# PowerModuleCell.net
KiCad netlist of a schematic drawn in Altium Designer
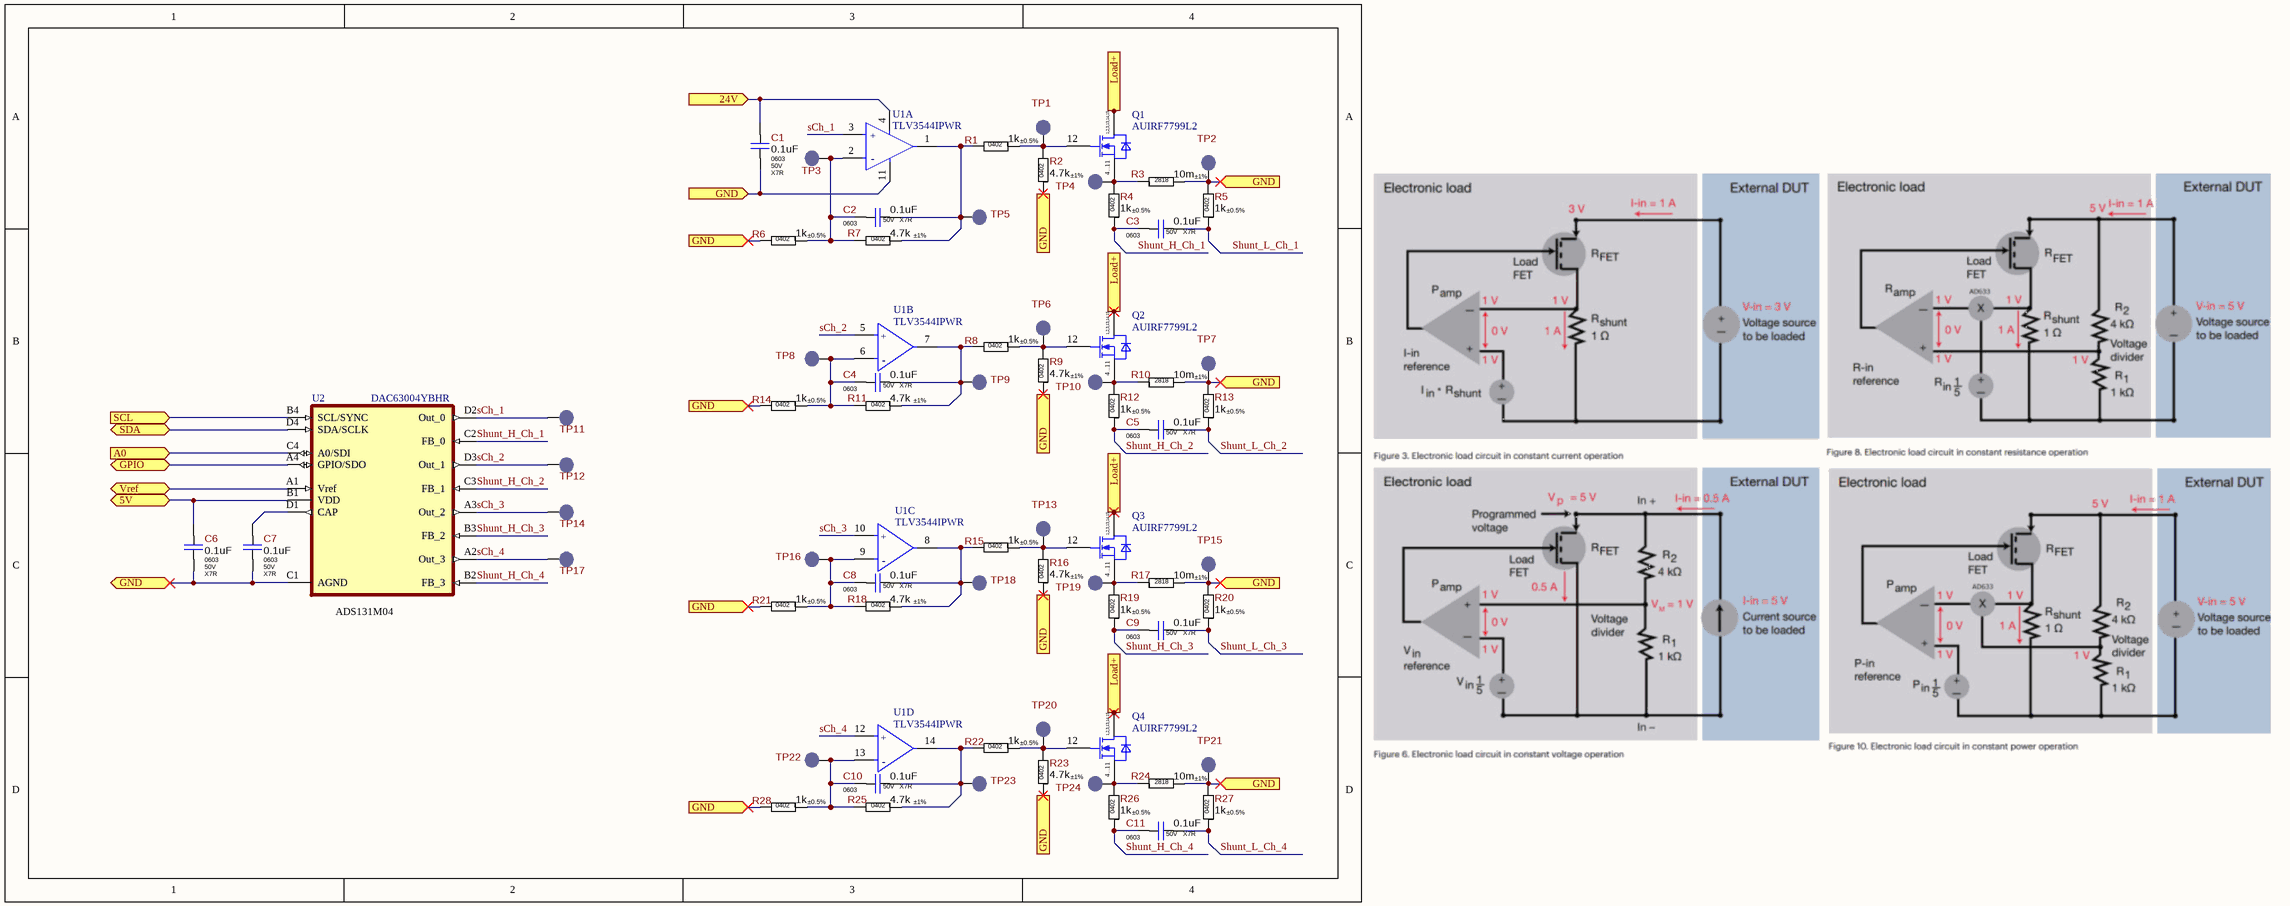
[diagram p0: PowerModuleCell.SchDoc]

(export (version "E")
  (design (tool "Eeschema 10.0.6"))
  (components
    (comp (ref "C1")
      (value "0.1uF")
      (footprint "C_CERAMIC_0603_MED")
      (description "100nF 50V X7R ±10% 0603 Ceramic Capacitor RoHS")
      (fields
        (field (name "PART NUMBER") "CL10B104KB8NNNC")
        (field (name "MANUFACTURER") "Samsung Electro-Mechanics")
        (field (name "PACKAGE") "0603")
        (field (name "VOLTAGE") "50V")
        (field (name "DIELECTRIC TYPE") "X7R")
      )
      (libsource (lib "EL.XXX.T01") (part "CL10B104KB8NNNC"))
    )
    (comp (ref "C2")
      (value "0.1uF")
      (footprint "C_CERAMIC_0603_MED")
      (description "100nF 50V X7R ±10% 0603 Ceramic Capacitor RoHS")
      (fields
        (field (name "PART NUMBER") "CL10B104KB8NNNC")
        (field (name "MANUFACTURER") "Samsung Electro-Mechanics")
        (field (name "PACKAGE") "0603")
        (field (name "VOLTAGE") "50V")
        (field (name "DIELECTRIC TYPE") "X7R")
      )
      (libsource (lib "EL.XXX.T01") (part "CL10B104KB8NNNC"))
    )
    (comp (ref "C3")
      (value "0.1uF")
      (footprint "C_CERAMIC_0603_MED")
      (description "100nF 50V X7R ±10% 0603 Ceramic Capacitor RoHS")
      (fields
        (field (name "PART NUMBER") "CL10B104KB8NNNC")
        (field (name "MANUFACTURER") "Samsung Electro-Mechanics")
        (field (name "PACKAGE") "0603")
        (field (name "VOLTAGE") "50V")
        (field (name "DIELECTRIC TYPE") "X7R")
      )
      (libsource (lib "EL.XXX.T01") (part "CL10B104KB8NNNC"))
    )
    (comp (ref "C4")
      (value "0.1uF")
      (footprint "C_CERAMIC_0603_MED")
      (description "100nF 50V X7R ±10% 0603 Ceramic Capacitor RoHS")
      (fields
        (field (name "PART NUMBER") "CL10B104KB8NNNC")
        (field (name "MANUFACTURER") "Samsung Electro-Mechanics")
        (field (name "PACKAGE") "0603")
        (field (name "VOLTAGE") "50V")
        (field (name "DIELECTRIC TYPE") "X7R")
      )
      (libsource (lib "EL.XXX.T01") (part "CL10B104KB8NNNC"))
    )
    (comp (ref "C5")
      (value "0.1uF")
      (footprint "C_CERAMIC_0603_MED")
      (description "100nF 50V X7R ±10% 0603 Ceramic Capacitor RoHS")
      (fields
        (field (name "PART NUMBER") "CL10B104KB8NNNC")
        (field (name "MANUFACTURER") "Samsung Electro-Mechanics")
        (field (name "PACKAGE") "0603")
        (field (name "VOLTAGE") "50V")
        (field (name "DIELECTRIC TYPE") "X7R")
      )
      (libsource (lib "EL.XXX.T01") (part "CL10B104KB8NNNC"))
    )
    (comp (ref "C6")
      (value "0.1uF")
      (footprint "C_CERAMIC_0603_MED")
      (description "100nF 50V X7R ±10% 0603 Ceramic Capacitor RoHS")
      (fields
        (field (name "PART NUMBER") "CL10B104KB8NNNC")
        (field (name "MANUFACTURER") "Samsung Electro-Mechanics")
        (field (name "PACKAGE") "0603")
        (field (name "VOLTAGE") "50V")
        (field (name "DIELECTRIC TYPE") "X7R")
      )
      (libsource (lib "EL.XXX.T01") (part "CL10B104KB8NNNC"))
    )
    (comp (ref "C7")
      (value "0.1uF")
      (footprint "C_CERAMIC_0603_MED")
      (description "100nF 50V X7R ±10% 0603 Ceramic Capacitor RoHS")
      (fields
        (field (name "PART NUMBER") "CL10B104KB8NNNC")
        (field (name "MANUFACTURER") "Samsung Electro-Mechanics")
        (field (name "PACKAGE") "0603")
        (field (name "VOLTAGE") "50V")
        (field (name "DIELECTRIC TYPE") "X7R")
      )
      (libsource (lib "EL.XXX.T01") (part "CL10B104KB8NNNC"))
    )
    (comp (ref "C8")
      (value "0.1uF")
      (footprint "C_CERAMIC_0603_MED")
      (description "100nF 50V X7R ±10% 0603 Ceramic Capacitor RoHS")
      (fields
        (field (name "PART NUMBER") "CL10B104KB8NNNC")
        (field (name "MANUFACTURER") "Samsung Electro-Mechanics")
        (field (name "PACKAGE") "0603")
        (field (name "VOLTAGE") "50V")
        (field (name "DIELECTRIC TYPE") "X7R")
      )
      (libsource (lib "EL.XXX.T01") (part "CL10B104KB8NNNC"))
    )
    (comp (ref "C9")
      (value "0.1uF")
      (footprint "C_CERAMIC_0603_MED")
      (description "100nF 50V X7R ±10% 0603 Ceramic Capacitor RoHS")
      (fields
        (field (name "PART NUMBER") "CL10B104KB8NNNC")
        (field (name "MANUFACTURER") "Samsung Electro-Mechanics")
        (field (name "PACKAGE") "0603")
        (field (name "VOLTAGE") "50V")
        (field (name "DIELECTRIC TYPE") "X7R")
      )
      (libsource (lib "EL.XXX.T01") (part "CL10B104KB8NNNC"))
    )
    (comp (ref "C10")
      (value "0.1uF")
      (footprint "C_CERAMIC_0603_MED")
      (description "100nF 50V X7R ±10% 0603 Ceramic Capacitor RoHS")
      (fields
        (field (name "PART NUMBER") "CL10B104KB8NNNC")
        (field (name "MANUFACTURER") "Samsung Electro-Mechanics")
        (field (name "PACKAGE") "0603")
        (field (name "VOLTAGE") "50V")
        (field (name "DIELECTRIC TYPE") "X7R")
      )
      (libsource (lib "EL.XXX.T01") (part "CL10B104KB8NNNC"))
    )
    (comp (ref "C11")
      (value "0.1uF")
      (footprint "C_CERAMIC_0603_MED")
      (description "100nF 50V X7R ±10% 0603 Ceramic Capacitor RoHS")
      (fields
        (field (name "PART NUMBER") "CL10B104KB8NNNC")
        (field (name "MANUFACTURER") "Samsung Electro-Mechanics")
        (field (name "PACKAGE") "0603")
        (field (name "VOLTAGE") "50V")
        (field (name "DIELECTRIC TYPE") "X7R")
      )
      (libsource (lib "EL.XXX.T01") (part "CL10B104KB8NNNC"))
    )
    (comp (ref "Q1")
      (value "AUIRF7799L2")
      (footprint "DIRECTFET-L8-V")
      (fields (field (name "PART NUMBER") "AUIRF7799L2TR") (field (name "MANUFACTURER") "Infineon"))
      (libsource (lib "EL.XXX.T01") (part "AUIRF7799L2"))
    )
    (comp (ref "Q2")
      (value "AUIRF7799L2")
      (footprint "DIRECTFET-L8-V")
      (fields (field (name "PART NUMBER") "AUIRF7799L2TR") (field (name "MANUFACTURER") "Infineon"))
      (libsource (lib "EL.XXX.T01") (part "AUIRF7799L2"))
    )
    (comp (ref "Q3")
      (value "AUIRF7799L2")
      (footprint "DIRECTFET-L8-V")
      (fields (field (name "PART NUMBER") "AUIRF7799L2TR") (field (name "MANUFACTURER") "Infineon"))
      (libsource (lib "EL.XXX.T01") (part "AUIRF7799L2"))
    )
    (comp (ref "Q4")
      (value "AUIRF7799L2")
      (footprint "DIRECTFET-L8-V")
      (fields (field (name "PART NUMBER") "AUIRF7799L2TR") (field (name "MANUFACTURER") "Infineon"))
      (libsource (lib "EL.XXX.T01") (part "AUIRF7799L2"))
    )
    (comp (ref "R1")
      (value "1k")
      (footprint "R_ANY_CHIP_0402_HI")
      (description "1 kOhms ±0.5% 1/16W 0402 Thick Film Resistor")
      (fields
        (field (name "PART NUMBER") "RC0402DR-071KL")
        (field (name "MANUFACTURER") "Yageo")
        (field (name "TOLERANCE") "±0.5%")
        (field (name "PACKAGE") "0402")
      )
      (libsource (lib "EL.XXX.T01") (part "RC0402DR-071KL"))
    )
    (comp (ref "R2")
      (value "4.7k")
      (footprint "R_ANY_CHIP_0402_HI")
      (description "4.7 kOhms ±1% 1/16W 0402 Thick Film Resistor")
      (fields
        (field (name "PART NUMBER") "RC0402FR-074K7L")
        (field (name "MANUFACTURER") "Yageo")
        (field (name "TOLERANCE") "±1%")
        (field (name "PACKAGE") "0402")
      )
      (libsource (lib "EL.XXX.T01") (part "RC0402FR-074K7L"))
    )
    (comp (ref "R3")
      (value "10m")
      (footprint "WSHP2818")
      (description "Current Sense Resistors - SMD 10W .010ohms 1%")
      (fields
        (field (name "PART NUMBER") "WSHP2818R0100FEA")
        (field (name "MANUFACTURER") "Vishay")
        (field (name "TOLERANCE") "±1%")
        (field (name "PACKAGE") "2818")
      )
      (libsource (lib "EL.XXX.T01") (part "WSHP2818R0100FEA"))
    )
    (comp (ref "R4")
      (value "1k")
      (footprint "R_ANY_CHIP_0402_HI")
      (description "1 kOhms ±0.5% 1/16W 0402 Thick Film Resistor")
      (fields
        (field (name "PART NUMBER") "RC0402DR-071KL")
        (field (name "MANUFACTURER") "Yageo")
        (field (name "TOLERANCE") "±0.5%")
        (field (name "PACKAGE") "0402")
      )
      (libsource (lib "EL.XXX.T01") (part "RC0402DR-071KL"))
    )
    (comp (ref "R5")
      (value "1k")
      (footprint "R_ANY_CHIP_0402_HI")
      (description "1 kOhms ±0.5% 1/16W 0402 Thick Film Resistor")
      (fields
        (field (name "PART NUMBER") "RC0402DR-071KL")
        (field (name "MANUFACTURER") "Yageo")
        (field (name "TOLERANCE") "±0.5%")
        (field (name "PACKAGE") "0402")
      )
      (libsource (lib "EL.XXX.T01") (part "RC0402DR-071KL"))
    )
    (comp (ref "R6")
      (value "1k")
      (footprint "R_ANY_CHIP_0402_HI")
      (description "1 kOhms ±0.5% 1/16W 0402 Thick Film Resistor")
      (fields
        (field (name "PART NUMBER") "RC0402DR-071KL")
        (field (name "MANUFACTURER") "Yageo")
        (field (name "TOLERANCE") "±0.5%")
        (field (name "PACKAGE") "0402")
      )
      (libsource (lib "EL.XXX.T01") (part "RC0402DR-071KL"))
    )
    (comp (ref "R7")
      (value "4.7k")
      (footprint "R_ANY_CHIP_0402_HI")
      (description "4.7 kOhms ±1% 1/16W 0402 Thick Film Resistor")
      (fields
        (field (name "PART NUMBER") "RC0402FR-074K7L")
        (field (name "MANUFACTURER") "Yageo")
        (field (name "TOLERANCE") "±1%")
        (field (name "PACKAGE") "0402")
      )
      (libsource (lib "EL.XXX.T01") (part "RC0402FR-074K7L"))
    )
    (comp (ref "R8")
      (value "1k")
      (footprint "R_ANY_CHIP_0402_HI")
      (description "1 kOhms ±0.5% 1/16W 0402 Thick Film Resistor")
      (fields
        (field (name "PART NUMBER") "RC0402DR-071KL")
        (field (name "MANUFACTURER") "Yageo")
        (field (name "TOLERANCE") "±0.5%")
        (field (name "PACKAGE") "0402")
      )
      (libsource (lib "EL.XXX.T01") (part "RC0402DR-071KL"))
    )
    (comp (ref "R9")
      (value "4.7k")
      (footprint "R_ANY_CHIP_0402_HI")
      (description "4.7 kOhms ±1% 1/16W 0402 Thick Film Resistor")
      (fields
        (field (name "PART NUMBER") "RC0402FR-074K7L")
        (field (name "MANUFACTURER") "Yageo")
        (field (name "TOLERANCE") "±1%")
        (field (name "PACKAGE") "0402")
      )
      (libsource (lib "EL.XXX.T01") (part "RC0402FR-074K7L"))
    )
    (comp (ref "R10")
      (value "10m")
      (footprint "WSHP2818")
      (description "Current Sense Resistors - SMD 10W .010ohms 1%")
      (fields
        (field (name "PART NUMBER") "WSHP2818R0100FEA")
        (field (name "MANUFACTURER") "Vishay")
        (field (name "TOLERANCE") "±1%")
        (field (name "PACKAGE") "2818")
      )
      (libsource (lib "EL.XXX.T01") (part "WSHP2818R0100FEA"))
    )
    (comp (ref "R11")
      (value "4.7k")
      (footprint "R_ANY_CHIP_0402_HI")
      (description "4.7 kOhms ±1% 1/16W 0402 Thick Film Resistor")
      (fields
        (field (name "PART NUMBER") "RC0402FR-074K7L")
        (field (name "MANUFACTURER") "Yageo")
        (field (name "TOLERANCE") "±1%")
        (field (name "PACKAGE") "0402")
      )
      (libsource (lib "EL.XXX.T01") (part "RC0402FR-074K7L"))
    )
    (comp (ref "R12")
      (value "1k")
      (footprint "R_ANY_CHIP_0402_HI")
      (description "1 kOhms ±0.5% 1/16W 0402 Thick Film Resistor")
      (fields
        (field (name "PART NUMBER") "RC0402DR-071KL")
        (field (name "MANUFACTURER") "Yageo")
        (field (name "TOLERANCE") "±0.5%")
        (field (name "PACKAGE") "0402")
      )
      (libsource (lib "EL.XXX.T01") (part "RC0402DR-071KL"))
    )
    (comp (ref "R13")
      (value "1k")
      (footprint "R_ANY_CHIP_0402_HI")
      (description "1 kOhms ±0.5% 1/16W 0402 Thick Film Resistor")
      (fields
        (field (name "PART NUMBER") "RC0402DR-071KL")
        (field (name "MANUFACTURER") "Yageo")
        (field (name "TOLERANCE") "±0.5%")
        (field (name "PACKAGE") "0402")
      )
      (libsource (lib "EL.XXX.T01") (part "RC0402DR-071KL"))
    )
    (comp (ref "R14")
      (value "1k")
      (footprint "R_ANY_CHIP_0402_HI")
      (description "1 kOhms ±0.5% 1/16W 0402 Thick Film Resistor")
      (fields
        (field (name "PART NUMBER") "RC0402DR-071KL")
        (field (name "MANUFACTURER") "Yageo")
        (field (name "TOLERANCE") "±0.5%")
        (field (name "PACKAGE") "0402")
      )
      (libsource (lib "EL.XXX.T01") (part "RC0402DR-071KL"))
    )
    (comp (ref "R15")
      (value "1k")
      (footprint "R_ANY_CHIP_0402_HI")
      (description "1 kOhms ±0.5% 1/16W 0402 Thick Film Resistor")
      (fields
        (field (name "PART NUMBER") "RC0402DR-071KL")
        (field (name "MANUFACTURER") "Yageo")
        (field (name "TOLERANCE") "±0.5%")
        (field (name "PACKAGE") "0402")
      )
      (libsource (lib "EL.XXX.T01") (part "RC0402DR-071KL"))
    )
    (comp (ref "R16")
      (value "4.7k")
      (footprint "R_ANY_CHIP_0402_HI")
      (description "4.7 kOhms ±1% 1/16W 0402 Thick Film Resistor")
      (fields
        (field (name "PART NUMBER") "RC0402FR-074K7L")
        (field (name "MANUFACTURER") "Yageo")
        (field (name "TOLERANCE") "±1%")
        (field (name "PACKAGE") "0402")
      )
      (libsource (lib "EL.XXX.T01") (part "RC0402FR-074K7L"))
    )
    (comp (ref "R17")
      (value "10m")
      (footprint "WSHP2818")
      (description "Current Sense Resistors - SMD 10W .010ohms 1%")
      (fields
        (field (name "PART NUMBER") "WSHP2818R0100FEA")
        (field (name "MANUFACTURER") "Vishay")
        (field (name "TOLERANCE") "±1%")
        (field (name "PACKAGE") "2818")
      )
      (libsource (lib "EL.XXX.T01") (part "WSHP2818R0100FEA"))
    )
    (comp (ref "R18")
      (value "4.7k")
      (footprint "R_ANY_CHIP_0402_HI")
      (description "4.7 kOhms ±1% 1/16W 0402 Thick Film Resistor")
      (fields
        (field (name "PART NUMBER") "RC0402FR-074K7L")
        (field (name "MANUFACTURER") "Yageo")
        (field (name "TOLERANCE") "±1%")
        (field (name "PACKAGE") "0402")
      )
      (libsource (lib "EL.XXX.T01") (part "RC0402FR-074K7L"))
    )
    (comp (ref "R19")
      (value "1k")
      (footprint "R_ANY_CHIP_0402_HI")
      (description "1 kOhms ±0.5% 1/16W 0402 Thick Film Resistor")
      (fields
        (field (name "PART NUMBER") "RC0402DR-071KL")
        (field (name "MANUFACTURER") "Yageo")
        (field (name "TOLERANCE") "±0.5%")
        (field (name "PACKAGE") "0402")
      )
      (libsource (lib "EL.XXX.T01") (part "RC0402DR-071KL"))
    )
    (comp (ref "R20")
      (value "1k")
      (footprint "R_ANY_CHIP_0402_HI")
      (description "1 kOhms ±0.5% 1/16W 0402 Thick Film Resistor")
      (fields
        (field (name "PART NUMBER") "RC0402DR-071KL")
        (field (name "MANUFACTURER") "Yageo")
        (field (name "TOLERANCE") "±0.5%")
        (field (name "PACKAGE") "0402")
      )
      (libsource (lib "EL.XXX.T01") (part "RC0402DR-071KL"))
    )
    (comp (ref "R21")
      (value "1k")
      (footprint "R_ANY_CHIP_0402_HI")
      (description "1 kOhms ±0.5% 1/16W 0402 Thick Film Resistor")
      (fields
        (field (name "PART NUMBER") "RC0402DR-071KL")
        (field (name "MANUFACTURER") "Yageo")
        (field (name "TOLERANCE") "±0.5%")
        (field (name "PACKAGE") "0402")
      )
      (libsource (lib "EL.XXX.T01") (part "RC0402DR-071KL"))
    )
    (comp (ref "R22")
      (value "1k")
      (footprint "R_ANY_CHIP_0402_HI")
      (description "1 kOhms ±0.5% 1/16W 0402 Thick Film Resistor")
      (fields
        (field (name "PART NUMBER") "RC0402DR-071KL")
        (field (name "MANUFACTURER") "Yageo")
        (field (name "TOLERANCE") "±0.5%")
        (field (name "PACKAGE") "0402")
      )
      (libsource (lib "EL.XXX.T01") (part "RC0402DR-071KL"))
    )
    (comp (ref "R23")
      (value "4.7k")
      (footprint "R_ANY_CHIP_0402_HI")
      (description "4.7 kOhms ±1% 1/16W 0402 Thick Film Resistor")
      (fields
        (field (name "PART NUMBER") "RC0402FR-074K7L")
        (field (name "MANUFACTURER") "Yageo")
        (field (name "TOLERANCE") "±1%")
        (field (name "PACKAGE") "0402")
      )
      (libsource (lib "EL.XXX.T01") (part "RC0402FR-074K7L"))
    )
    (comp (ref "R24")
      (value "10m")
      (footprint "WSHP2818")
      (description "Current Sense Resistors - SMD 10W .010ohms 1%")
      (fields
        (field (name "PART NUMBER") "WSHP2818R0100FEA")
        (field (name "MANUFACTURER") "Vishay")
        (field (name "TOLERANCE") "±1%")
        (field (name "PACKAGE") "2818")
      )
      (libsource (lib "EL.XXX.T01") (part "WSHP2818R0100FEA"))
    )
    (comp (ref "R25")
      (value "4.7k")
      (footprint "R_ANY_CHIP_0402_HI")
      (description "4.7 kOhms ±1% 1/16W 0402 Thick Film Resistor")
      (fields
        (field (name "PART NUMBER") "RC0402FR-074K7L")
        (field (name "MANUFACTURER") "Yageo")
        (field (name "TOLERANCE") "±1%")
        (field (name "PACKAGE") "0402")
      )
      (libsource (lib "EL.XXX.T01") (part "RC0402FR-074K7L"))
    )
    (comp (ref "R26")
      (value "1k")
      (footprint "R_ANY_CHIP_0402_HI")
      (description "1 kOhms ±0.5% 1/16W 0402 Thick Film Resistor")
      (fields
        (field (name "PART NUMBER") "RC0402DR-071KL")
        (field (name "MANUFACTURER") "Yageo")
        (field (name "TOLERANCE") "±0.5%")
        (field (name "PACKAGE") "0402")
      )
      (libsource (lib "EL.XXX.T01") (part "RC0402DR-071KL"))
    )
    (comp (ref "R27")
      (value "1k")
      (footprint "R_ANY_CHIP_0402_HI")
      (description "1 kOhms ±0.5% 1/16W 0402 Thick Film Resistor")
      (fields
        (field (name "PART NUMBER") "RC0402DR-071KL")
        (field (name "MANUFACTURER") "Yageo")
        (field (name "TOLERANCE") "±0.5%")
        (field (name "PACKAGE") "0402")
      )
      (libsource (lib "EL.XXX.T01") (part "RC0402DR-071KL"))
    )
    (comp (ref "R28")
      (value "1k")
      (footprint "R_ANY_CHIP_0402_HI")
      (description "1 kOhms ±0.5% 1/16W 0402 Thick Film Resistor")
      (fields
        (field (name "PART NUMBER") "RC0402DR-071KL")
        (field (name "MANUFACTURER") "Yageo")
        (field (name "TOLERANCE") "±0.5%")
        (field (name "PACKAGE") "0402")
      )
      (libsource (lib "EL.XXX.T01") (part "RC0402DR-071KL"))
    )
    (comp (ref "TP1")
      (value "LED_LINK")
      (footprint "TP_SMD_2mm")
      (description "Test Point SMD Pad 1.0mm/1.5mm/2mm")
      (fields (field (name "PART NUMBER") "TP-PAD-SMD"))
      (libsource (lib "EL.XXX.T01") (part "Test-Point-SMD-1"))
    )
    (comp (ref "TP2")
      (value "LED_LINK")
      (footprint "TP_SMD_2mm")
      (description "Test Point SMD Pad 1.0mm/1.5mm/2mm")
      (fields (field (name "PART NUMBER") "TP-PAD-SMD"))
      (libsource (lib "EL.XXX.T01") (part "Test-Point-SMD-1"))
    )
    (comp (ref "TP3")
      (value "LED_LINK")
      (footprint "TP_SMD_2mm")
      (description "Test Point SMD Pad 1.0mm/1.5mm/2mm")
      (fields (field (name "PART NUMBER") "TP-PAD-SMD"))
      (libsource (lib "EL.XXX.T01") (part "Test-Point-SMD-1"))
    )
    (comp (ref "TP4")
      (value "LED_LINK")
      (footprint "TP_SMD_2mm")
      (description "Test Point SMD Pad 1.0mm/1.5mm/2mm")
      (fields (field (name "PART NUMBER") "TP-PAD-SMD"))
      (libsource (lib "EL.XXX.T01") (part "Test-Point-SMD-1"))
    )
    (comp (ref "TP5")
      (value "LED_LINK")
      (footprint "TP_SMD_2mm")
      (description "Test Point SMD Pad 1.0mm/1.5mm/2mm")
      (fields (field (name "PART NUMBER") "TP-PAD-SMD"))
      (libsource (lib "EL.XXX.T01") (part "Test-Point-SMD-1"))
    )
    (comp (ref "TP6")
      (value "LED_LINK")
      (footprint "TP_SMD_2mm")
      (description "Test Point SMD Pad 1.0mm/1.5mm/2mm")
      (fields (field (name "PART NUMBER") "TP-PAD-SMD"))
      (libsource (lib "EL.XXX.T01") (part "Test-Point-SMD-1"))
    )
    (comp (ref "TP7")
      (value "LED_LINK")
      (footprint "TP_SMD_2mm")
      (description "Test Point SMD Pad 1.0mm/1.5mm/2mm")
      (fields (field (name "PART NUMBER") "TP-PAD-SMD"))
      (libsource (lib "EL.XXX.T01") (part "Test-Point-SMD-1"))
    )
    (comp (ref "TP8")
      (value "LED_LINK")
      (footprint "TP_SMD_2mm")
      (description "Test Point SMD Pad 1.0mm/1.5mm/2mm")
      (fields (field (name "PART NUMBER") "TP-PAD-SMD"))
      (libsource (lib "EL.XXX.T01") (part "Test-Point-SMD-1"))
    )
    (comp (ref "TP9")
      (value "LED_LINK")
      (footprint "TP_SMD_2mm")
      (description "Test Point SMD Pad 1.0mm/1.5mm/2mm")
      (fields (field (name "PART NUMBER") "TP-PAD-SMD"))
      (libsource (lib "EL.XXX.T01") (part "Test-Point-SMD-1"))
    )
    (comp (ref "TP10")
      (value "LED_LINK")
      (footprint "TP_SMD_2mm")
      (description "Test Point SMD Pad 1.0mm/1.5mm/2mm")
      (fields (field (name "PART NUMBER") "TP-PAD-SMD"))
      (libsource (lib "EL.XXX.T01") (part "Test-Point-SMD-1"))
    )
    (comp (ref "TP11")
      (value "LED_LINK")
      (footprint "TP_SMD_2mm")
      (description "Test Point SMD Pad 1.0mm/1.5mm/2mm")
      (fields (field (name "PART NUMBER") "TP-PAD-SMD"))
      (libsource (lib "EL.XXX.T01") (part "Test-Point-SMD-1"))
    )
    (comp (ref "TP12")
      (value "LED_LINK")
      (footprint "TP_SMD_2mm")
      (description "Test Point SMD Pad 1.0mm/1.5mm/2mm")
      (fields (field (name "PART NUMBER") "TP-PAD-SMD"))
      (libsource (lib "EL.XXX.T01") (part "Test-Point-SMD-1"))
    )
    (comp (ref "TP13")
      (value "LED_LINK")
      (footprint "TP_SMD_2mm")
      (description "Test Point SMD Pad 1.0mm/1.5mm/2mm")
      (fields (field (name "PART NUMBER") "TP-PAD-SMD"))
      (libsource (lib "EL.XXX.T01") (part "Test-Point-SMD-1"))
    )
    (comp (ref "TP14")
      (value "LED_LINK")
      (footprint "TP_SMD_2mm")
      (description "Test Point SMD Pad 1.0mm/1.5mm/2mm")
      (fields (field (name "PART NUMBER") "TP-PAD-SMD"))
      (libsource (lib "EL.XXX.T01") (part "Test-Point-SMD-1"))
    )
    (comp (ref "TP15")
      (value "LED_LINK")
      (footprint "TP_SMD_2mm")
      (description "Test Point SMD Pad 1.0mm/1.5mm/2mm")
      (fields (field (name "PART NUMBER") "TP-PAD-SMD"))
      (libsource (lib "EL.XXX.T01") (part "Test-Point-SMD-1"))
    )
    (comp (ref "TP16")
      (value "LED_LINK")
      (footprint "TP_SMD_2mm")
      (description "Test Point SMD Pad 1.0mm/1.5mm/2mm")
      (fields (field (name "PART NUMBER") "TP-PAD-SMD"))
      (libsource (lib "EL.XXX.T01") (part "Test-Point-SMD-1"))
    )
    (comp (ref "TP17")
      (value "LED_LINK")
      (footprint "TP_SMD_2mm")
      (description "Test Point SMD Pad 1.0mm/1.5mm/2mm")
      (fields (field (name "PART NUMBER") "TP-PAD-SMD"))
      (libsource (lib "EL.XXX.T01") (part "Test-Point-SMD-1"))
    )
    (comp (ref "TP18")
      (value "LED_LINK")
      (footprint "TP_SMD_2mm")
      (description "Test Point SMD Pad 1.0mm/1.5mm/2mm")
      (fields (field (name "PART NUMBER") "TP-PAD-SMD"))
      (libsource (lib "EL.XXX.T01") (part "Test-Point-SMD-1"))
    )
    (comp (ref "TP19")
      (value "LED_LINK")
      (footprint "TP_SMD_2mm")
      (description "Test Point SMD Pad 1.0mm/1.5mm/2mm")
      (fields (field (name "PART NUMBER") "TP-PAD-SMD"))
      (libsource (lib "EL.XXX.T01") (part "Test-Point-SMD-1"))
    )
    (comp (ref "TP20")
      (value "LED_LINK")
      (footprint "TP_SMD_2mm")
      (description "Test Point SMD Pad 1.0mm/1.5mm/2mm")
      (fields (field (name "PART NUMBER") "TP-PAD-SMD"))
      (libsource (lib "EL.XXX.T01") (part "Test-Point-SMD-1"))
    )
    (comp (ref "TP21")
      (value "LED_LINK")
      (footprint "TP_SMD_2mm")
      (description "Test Point SMD Pad 1.0mm/1.5mm/2mm")
      (fields (field (name "PART NUMBER") "TP-PAD-SMD"))
      (libsource (lib "EL.XXX.T01") (part "Test-Point-SMD-1"))
    )
    (comp (ref "TP22")
      (value "LED_LINK")
      (footprint "TP_SMD_2mm")
      (description "Test Point SMD Pad 1.0mm/1.5mm/2mm")
      (fields (field (name "PART NUMBER") "TP-PAD-SMD"))
      (libsource (lib "EL.XXX.T01") (part "Test-Point-SMD-1"))
    )
    (comp (ref "TP23")
      (value "LED_LINK")
      (footprint "TP_SMD_2mm")
      (description "Test Point SMD Pad 1.0mm/1.5mm/2mm")
      (fields (field (name "PART NUMBER") "TP-PAD-SMD"))
      (libsource (lib "EL.XXX.T01") (part "Test-Point-SMD-1"))
    )
    (comp (ref "TP24")
      (value "LED_LINK")
      (footprint "TP_SMD_2mm")
      (description "Test Point SMD Pad 1.0mm/1.5mm/2mm")
      (fields (field (name "PART NUMBER") "TP-PAD-SMD"))
      (libsource (lib "EL.XXX.T01") (part "Test-Point-SMD-1"))
    )
    (comp (ref "U1")
      (value "TLV3544IPWR")
      (footprint "TSSOP-14")
      (description "Operational Amplifiers - Op Amps Quad 200MHz RRIO CMOS Operational Amp")
      (libsource (lib "EL.XXX.T01") (part "TLV3544IPWR"))
    )
    (comp (ref "U2")
      (value "DAC63004YBHR")
      (footprint "BGA16C50P4X4_200X200X60")
      (description "Digital to Analog Converters - DAC Ultra-low-power four -channel 12-bit smar")
      (libsource (lib "EL.XXX.T01") (part "DAC63004YBHR"))
    )
  )
  (nets
    (net (code "1") (name "/5V") (class "Default")
      (node (ref "C6") (pin "2") (pinfunction "2_2") (pintype "passive"))
      (node (ref "U2") (pin "B1") (pinfunction "VDD_B1") (pintype "power_in"))
    )
    (net (code "2") (name "/24V") (class "Default")
      (node (ref "C1") (pin "2") (pinfunction "2_2") (pintype "passive"))
      (node (ref "U1") (pin "4") (pinfunction "V+_4") (pintype "power_in"))
    )
    (net (code "3") (name "/A0") (class "Default")
      (node (ref "U2") (pin "C4") (pinfunction "A0/SDI_C4") (pintype "bidirectional"))
    )
    (net (code "4") (name "/GND") (class "Default")
      (node (ref "C1") (pin "1") (pinfunction "1_1") (pintype "passive"))
      (node (ref "C6") (pin "1") (pinfunction "1_1") (pintype "passive"))
      (node (ref "C7") (pin "1") (pinfunction "1_1") (pintype "passive"))
      (node (ref "R10") (pin "1") (pintype "passive"))
      (node (ref "R13") (pin "1") (pintype "passive"))
      (node (ref "R14") (pin "1") (pintype "passive"))
      (node (ref "R16") (pin "2") (pintype "passive"))
      (node (ref "R17") (pin "1") (pintype "passive"))
      (node (ref "R2") (pin "2") (pintype "passive"))
      (node (ref "R20") (pin "1") (pintype "passive"))
      (node (ref "R21") (pin "1") (pintype "passive"))
      (node (ref "R23") (pin "2") (pintype "passive"))
      (node (ref "R24") (pin "1") (pintype "passive"))
      (node (ref "R27") (pin "1") (pintype "passive"))
      (node (ref "R28") (pin "1") (pintype "passive"))
      (node (ref "R3") (pin "1") (pintype "passive"))
      (node (ref "R5") (pin "1") (pintype "passive"))
      (node (ref "R6") (pin "1") (pintype "passive"))
      (node (ref "R9") (pin "2") (pintype "passive"))
      (node (ref "TP15") (pin "1") (pintype "passive"))
      (node (ref "TP2") (pin "1") (pintype "passive"))
      (node (ref "TP21") (pin "1") (pintype "passive"))
      (node (ref "TP7") (pin "1") (pintype "passive"))
      (node (ref "U1") (pin "11") (pinfunction "V-_11") (pintype "power_in"))
      (node (ref "U2") (pin "C1") (pinfunction "AGND_C1") (pintype "power_in"))
    )
    (net (code "5") (name "/GPIO") (class "Default")
      (node (ref "U2") (pin "A4") (pinfunction "GPIO/SDO_A4") (pintype "bidirectional"))
    )
    (net (code "6") (name "/Load+") (class "Default")
      (node (ref "Q1") (pin "1") (pinfunction "DRAIN1_1") (pintype "passive"))
      (node (ref "Q1") (pin "13") (pinfunction "DRAIN4_13") (pintype "passive"))
      (node (ref "Q1") (pin "14") (pinfunction "DRAIN5_14") (pintype "passive"))
      (node (ref "Q1") (pin "15") (pinfunction "DRAIN6_15") (pintype "passive"))
      (node (ref "Q1") (pin "2") (pinfunction "DRAIN2_2") (pintype "passive"))
      (node (ref "Q1") (pin "3") (pinfunction "DRAIN3_3") (pintype "passive"))
      (node (ref "Q2") (pin "1") (pinfunction "DRAIN1_1") (pintype "passive"))
      (node (ref "Q2") (pin "13") (pinfunction "DRAIN4_13") (pintype "passive"))
      (node (ref "Q2") (pin "14") (pinfunction "DRAIN5_14") (pintype "passive"))
      (node (ref "Q2") (pin "15") (pinfunction "DRAIN6_15") (pintype "passive"))
      (node (ref "Q2") (pin "2") (pinfunction "DRAIN2_2") (pintype "passive"))
      (node (ref "Q2") (pin "3") (pinfunction "DRAIN3_3") (pintype "passive"))
      (node (ref "Q3") (pin "1") (pinfunction "DRAIN1_1") (pintype "passive"))
      (node (ref "Q3") (pin "13") (pinfunction "DRAIN4_13") (pintype "passive"))
      (node (ref "Q3") (pin "14") (pinfunction "DRAIN5_14") (pintype "passive"))
      (node (ref "Q3") (pin "15") (pinfunction "DRAIN6_15") (pintype "passive"))
      (node (ref "Q3") (pin "2") (pinfunction "DRAIN2_2") (pintype "passive"))
      (node (ref "Q3") (pin "3") (pinfunction "DRAIN3_3") (pintype "passive"))
      (node (ref "Q4") (pin "1") (pinfunction "DRAIN1_1") (pintype "passive"))
      (node (ref "Q4") (pin "13") (pinfunction "DRAIN4_13") (pintype "passive"))
      (node (ref "Q4") (pin "14") (pinfunction "DRAIN5_14") (pintype "passive"))
      (node (ref "Q4") (pin "15") (pinfunction "DRAIN6_15") (pintype "passive"))
      (node (ref "Q4") (pin "2") (pinfunction "DRAIN2_2") (pintype "passive"))
      (node (ref "Q4") (pin "3") (pinfunction "DRAIN3_3") (pintype "passive"))
    )
    (net (code "7") (name "/SCL") (class "Default")
      (node (ref "U2") (pin "B4") (pinfunction "SCL/SYNC_B4") (pintype "input"))
    )
    (net (code "8") (name "/SDA") (class "Default")
      (node (ref "U2") (pin "D4") (pinfunction "SDA/SCLK_D4") (pintype "input"))
    )
    (net (code "9") (name "/Shunt_H_Ch_1") (class "Default")
      (node (ref "C3") (pin "1") (pinfunction "1_1") (pintype "passive"))
      (node (ref "R4") (pin "2") (pintype "passive"))
      (node (ref "U2") (pin "C2") (pinfunction "FB_0_C2") (pintype "input"))
    )
    (net (code "10") (name "/Shunt_H_Ch_2") (class "Default")
      (node (ref "C5") (pin "1") (pinfunction "1_1") (pintype "passive"))
      (node (ref "R12") (pin "2") (pintype "passive"))
      (node (ref "U2") (pin "C3") (pinfunction "FB_1_C3") (pintype "input"))
    )
    (net (code "11") (name "/Shunt_H_Ch_3") (class "Default")
      (node (ref "C9") (pin "1") (pinfunction "1_1") (pintype "passive"))
      (node (ref "R19") (pin "2") (pintype "passive"))
      (node (ref "U2") (pin "B3") (pinfunction "FB_2_B3") (pintype "input"))
    )
    (net (code "12") (name "/Shunt_H_Ch_4") (class "Default")
      (node (ref "C11") (pin "1") (pinfunction "1_1") (pintype "passive"))
      (node (ref "R26") (pin "2") (pintype "passive"))
      (node (ref "U2") (pin "B2") (pinfunction "FB_3_B2") (pintype "input"))
    )
    (net (code "13") (name "/Shunt_L_Ch_1") (class "Default")
      (node (ref "C3") (pin "2") (pinfunction "2_2") (pintype "passive"))
      (node (ref "R5") (pin "2") (pintype "passive"))
    )
    (net (code "14") (name "/Shunt_L_Ch_2") (class "Default")
      (node (ref "C5") (pin "2") (pinfunction "2_2") (pintype "passive"))
      (node (ref "R13") (pin "2") (pintype "passive"))
    )
    (net (code "15") (name "/Shunt_L_Ch_3") (class "Default")
      (node (ref "C9") (pin "2") (pinfunction "2_2") (pintype "passive"))
      (node (ref "R20") (pin "2") (pintype "passive"))
    )
    (net (code "16") (name "/Shunt_L_Ch_4") (class "Default")
      (node (ref "C11") (pin "2") (pinfunction "2_2") (pintype "passive"))
      (node (ref "R27") (pin "2") (pintype "passive"))
    )
    (net (code "17") (name "/Vref") (class "Default")
      (node (ref "U2") (pin "A1") (pinfunction "Vref_A1") (pintype "input"))
    )
    (net (code "18") (name "/sCh_1") (class "Default")
      (node (ref "TP11") (pin "1") (pintype "passive"))
      (node (ref "U1") (pin "3") (pinfunction "+IN_A_3") (pintype "tri_state"))
      (node (ref "U2") (pin "D2") (pinfunction "Out_0_D2") (pintype "output"))
    )
    (net (code "19") (name "/sCh_2") (class "Default")
      (node (ref "TP12") (pin "1") (pintype "passive"))
      (node (ref "U1") (pin "5") (pinfunction "+IN_B_5") (pintype "tri_state"))
      (node (ref "U2") (pin "D3") (pinfunction "Out_1_D3") (pintype "output"))
    )
    (net (code "20") (name "/sCh_3") (class "Default")
      (node (ref "TP14") (pin "1") (pintype "passive"))
      (node (ref "U1") (pin "10") (pinfunction "+IN_C_10") (pintype "tri_state"))
      (node (ref "U2") (pin "A3") (pinfunction "Out_2_A3") (pintype "output"))
    )
    (net (code "21") (name "/sCh_4") (class "Default")
      (node (ref "TP17") (pin "1") (pintype "passive"))
      (node (ref "U1") (pin "12") (pinfunction "+IN_D_12") (pintype "tri_state"))
      (node (ref "U2") (pin "A2") (pinfunction "Out_3_A2") (pintype "output"))
    )
    (net (code "22") (name "Net-(Q1-GATE)") (class "Default")
      (node (ref "Q1") (pin "12") (pinfunction "GATE_12") (pintype "passive"))
      (node (ref "R1") (pin "2") (pintype "passive"))
      (node (ref "R2") (pin "1") (pintype "passive"))
      (node (ref "TP1") (pin "1") (pintype "passive"))
    )
    (net (code "23") (name "Net-(Q1-SOURCE1)") (class "Default")
      (node (ref "Q1") (pin "10") (pinfunction "SOURCE7_10") (pintype "passive"))
      (node (ref "Q1") (pin "11") (pinfunction "SOURCE8_11") (pintype "passive"))
      (node (ref "Q1") (pin "4") (pinfunction "SOURCE1_4") (pintype "passive"))
      (node (ref "Q1") (pin "5") (pinfunction "SOURCE2_5") (pintype "passive"))
      (node (ref "Q1") (pin "6") (pinfunction "SOURCE3_6") (pintype "passive"))
      (node (ref "Q1") (pin "7") (pinfunction "SOURCE4_7") (pintype "passive"))
      (node (ref "Q1") (pin "8") (pinfunction "SOURCE5_8") (pintype "passive"))
      (node (ref "Q1") (pin "9") (pinfunction "SOURCE6_9") (pintype "passive"))
      (node (ref "R3") (pin "2") (pintype "passive"))
      (node (ref "R4") (pin "1") (pintype "passive"))
      (node (ref "TP4") (pin "1") (pintype "passive"))
    )
    (net (code "24") (name "Net-(Q2-GATE)") (class "Default")
      (node (ref "Q2") (pin "12") (pinfunction "GATE_12") (pintype "passive"))
      (node (ref "R8") (pin "2") (pintype "passive"))
      (node (ref "R9") (pin "1") (pintype "passive"))
      (node (ref "TP6") (pin "1") (pintype "passive"))
    )
    (net (code "25") (name "Net-(Q2-SOURCE1)") (class "Default")
      (node (ref "Q2") (pin "10") (pinfunction "SOURCE7_10") (pintype "passive"))
      (node (ref "Q2") (pin "11") (pinfunction "SOURCE8_11") (pintype "passive"))
      (node (ref "Q2") (pin "4") (pinfunction "SOURCE1_4") (pintype "passive"))
      (node (ref "Q2") (pin "5") (pinfunction "SOURCE2_5") (pintype "passive"))
      (node (ref "Q2") (pin "6") (pinfunction "SOURCE3_6") (pintype "passive"))
      (node (ref "Q2") (pin "7") (pinfunction "SOURCE4_7") (pintype "passive"))
      (node (ref "Q2") (pin "8") (pinfunction "SOURCE5_8") (pintype "passive"))
      (node (ref "Q2") (pin "9") (pinfunction "SOURCE6_9") (pintype "passive"))
      (node (ref "R10") (pin "2") (pintype "passive"))
      (node (ref "R12") (pin "1") (pintype "passive"))
      (node (ref "TP10") (pin "1") (pintype "passive"))
    )
    (net (code "26") (name "Net-(Q3-GATE)") (class "Default")
      (node (ref "Q3") (pin "12") (pinfunction "GATE_12") (pintype "passive"))
      (node (ref "R15") (pin "2") (pintype "passive"))
      (node (ref "R16") (pin "1") (pintype "passive"))
      (node (ref "TP13") (pin "1") (pintype "passive"))
    )
    (net (code "27") (name "Net-(Q3-SOURCE1)") (class "Default")
      (node (ref "Q3") (pin "10") (pinfunction "SOURCE7_10") (pintype "passive"))
      (node (ref "Q3") (pin "11") (pinfunction "SOURCE8_11") (pintype "passive"))
      (node (ref "Q3") (pin "4") (pinfunction "SOURCE1_4") (pintype "passive"))
      (node (ref "Q3") (pin "5") (pinfunction "SOURCE2_5") (pintype "passive"))
      (node (ref "Q3") (pin "6") (pinfunction "SOURCE3_6") (pintype "passive"))
      (node (ref "Q3") (pin "7") (pinfunction "SOURCE4_7") (pintype "passive"))
      (node (ref "Q3") (pin "8") (pinfunction "SOURCE5_8") (pintype "passive"))
      (node (ref "Q3") (pin "9") (pinfunction "SOURCE6_9") (pintype "passive"))
      (node (ref "R17") (pin "2") (pintype "passive"))
      (node (ref "R19") (pin "1") (pintype "passive"))
      (node (ref "TP19") (pin "1") (pintype "passive"))
    )
    (net (code "28") (name "Net-(Q4-GATE)") (class "Default")
      (node (ref "Q4") (pin "12") (pinfunction "GATE_12") (pintype "passive"))
      (node (ref "R22") (pin "2") (pintype "passive"))
      (node (ref "R23") (pin "1") (pintype "passive"))
      (node (ref "TP20") (pin "1") (pintype "passive"))
    )
    (net (code "29") (name "Net-(Q4-SOURCE1)") (class "Default")
      (node (ref "Q4") (pin "10") (pinfunction "SOURCE7_10") (pintype "passive"))
      (node (ref "Q4") (pin "11") (pinfunction "SOURCE8_11") (pintype "passive"))
      (node (ref "Q4") (pin "4") (pinfunction "SOURCE1_4") (pintype "passive"))
      (node (ref "Q4") (pin "5") (pinfunction "SOURCE2_5") (pintype "passive"))
      (node (ref "Q4") (pin "6") (pinfunction "SOURCE3_6") (pintype "passive"))
      (node (ref "Q4") (pin "7") (pinfunction "SOURCE4_7") (pintype "passive"))
      (node (ref "Q4") (pin "8") (pinfunction "SOURCE5_8") (pintype "passive"))
      (node (ref "Q4") (pin "9") (pinfunction "SOURCE6_9") (pintype "passive"))
      (node (ref "R24") (pin "2") (pintype "passive"))
      (node (ref "R26") (pin "1") (pintype "passive"))
      (node (ref "TP24") (pin "1") (pintype "passive"))
    )
    (net (code "30") (name "Net-(U1A--IN_A)") (class "Default")
      (node (ref "C2") (pin "1") (pinfunction "1_1") (pintype "passive"))
      (node (ref "R6") (pin "2") (pintype "passive"))
      (node (ref "R7") (pin "1") (pintype "passive"))
      (node (ref "TP3") (pin "1") (pintype "passive"))
      (node (ref "U1") (pin "2") (pinfunction "-IN_A_2") (pintype "tri_state"))
    )
    (net (code "31") (name "Net-(U1A-OUT_A)") (class "Default")
      (node (ref "C2") (pin "2") (pinfunction "2_2") (pintype "passive"))
      (node (ref "R1") (pin "1") (pintype "passive"))
      (node (ref "R7") (pin "2") (pintype "passive"))
      (node (ref "TP5") (pin "1") (pintype "passive"))
      (node (ref "U1") (pin "1") (pinfunction "OUT_A_1") (pintype "passive"))
    )
    (net (code "32") (name "Net-(U1B--IN_B)") (class "Default")
      (node (ref "C4") (pin "1") (pinfunction "1_1") (pintype "passive"))
      (node (ref "R11") (pin "1") (pintype "passive"))
      (node (ref "R14") (pin "2") (pintype "passive"))
      (node (ref "TP8") (pin "1") (pintype "passive"))
      (node (ref "U1") (pin "6") (pinfunction "-IN_B_6") (pintype "tri_state"))
    )
    (net (code "33") (name "Net-(U1B-OUT_B)") (class "Default")
      (node (ref "C4") (pin "2") (pinfunction "2_2") (pintype "passive"))
      (node (ref "R11") (pin "2") (pintype "passive"))
      (node (ref "R8") (pin "1") (pintype "passive"))
      (node (ref "TP9") (pin "1") (pintype "passive"))
      (node (ref "U1") (pin "7") (pinfunction "OUT_B_7") (pintype "passive"))
    )
    (net (code "34") (name "Net-(U1C--IN_C)") (class "Default")
      (node (ref "C8") (pin "1") (pinfunction "1_1") (pintype "passive"))
      (node (ref "R18") (pin "1") (pintype "passive"))
      (node (ref "R21") (pin "2") (pintype "passive"))
      (node (ref "TP16") (pin "1") (pintype "passive"))
      (node (ref "U1") (pin "9") (pinfunction "-IN_C_9") (pintype "tri_state"))
    )
    (net (code "35") (name "Net-(U1C-OUT_C)") (class "Default")
      (node (ref "C8") (pin "2") (pinfunction "2_2") (pintype "passive"))
      (node (ref "R15") (pin "1") (pintype "passive"))
      (node (ref "R18") (pin "2") (pintype "passive"))
      (node (ref "TP18") (pin "1") (pintype "passive"))
      (node (ref "U1") (pin "8") (pinfunction "OUT_C_8") (pintype "passive"))
    )
    (net (code "36") (name "Net-(U1D--IN_D)") (class "Default")
      (node (ref "C10") (pin "1") (pinfunction "1_1") (pintype "passive"))
      (node (ref "R25") (pin "1") (pintype "passive"))
      (node (ref "R28") (pin "2") (pintype "passive"))
      (node (ref "TP22") (pin "1") (pintype "passive"))
      (node (ref "U1") (pin "13") (pinfunction "-IN_D_13") (pintype "tri_state"))
    )
    (net (code "37") (name "Net-(U1D-OUT_D)") (class "Default")
      (node (ref "C10") (pin "2") (pinfunction "2_2") (pintype "passive"))
      (node (ref "R22") (pin "1") (pintype "passive"))
      (node (ref "R25") (pin "2") (pintype "passive"))
      (node (ref "TP23") (pin "1") (pintype "passive"))
      (node (ref "U1") (pin "14") (pinfunction "OUT_D_14") (pintype "passive"))
    )
    (net (code "38") (name "Net-(U2-CAP)") (class "Default")
      (node (ref "C7") (pin "2") (pinfunction "2_2") (pintype "passive"))
      (node (ref "U2") (pin "D1") (pinfunction "CAP_D1") (pintype "output"))
    )
  )
)
